# arm-pro-mini.net
KiCad netlist of a schematic drawn in EAGLE
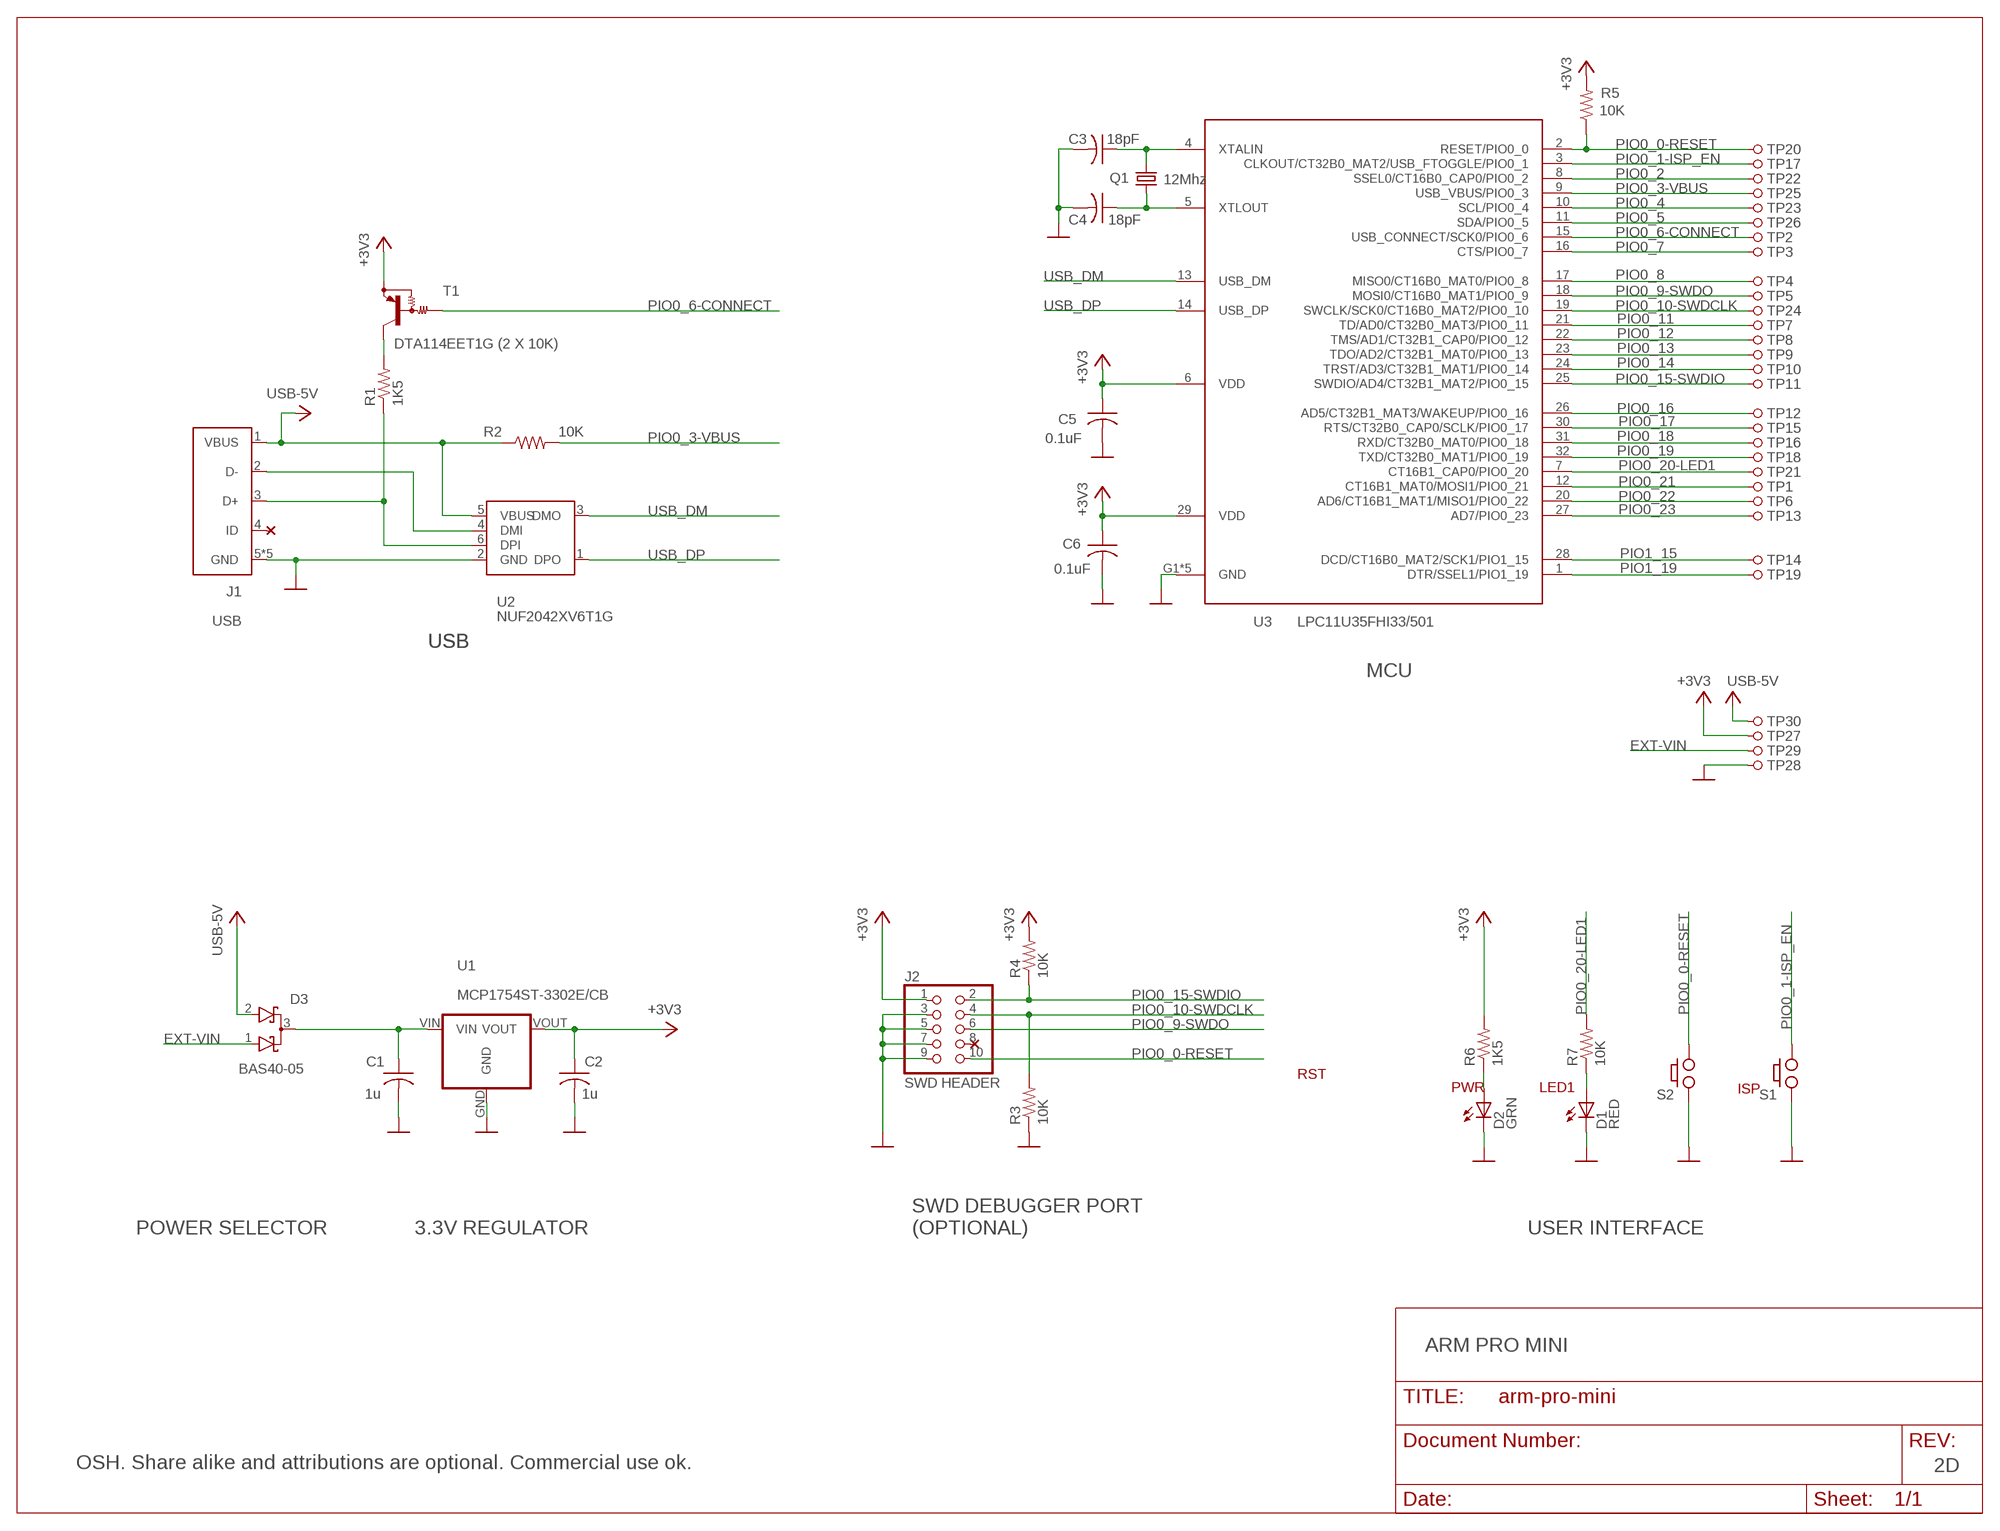
[diagram p0: schematic, sheet 1]

(export (version "E")
  (design (tool "Eeschema 10.0.6"))
  (components
    (comp (ref "C1")
      (value "1u")
      (footprint "eagle-import:C0603K")
      (libsource (lib "eagle-import") (part "CAPACITORC0603K"))
    )
    (comp (ref "C2")
      (value "1u")
      (footprint "eagle-import:C0603K")
      (libsource (lib "eagle-import") (part "CAPACITORC0603K"))
    )
    (comp (ref "C3")
      (value "18pF")
      (footprint "eagle-import:C0402K")
      (libsource (lib "eagle-import") (part "C-USC0402K"))
    )
    (comp (ref "C4")
      (value "18pF")
      (footprint "eagle-import:C0402K")
      (libsource (lib "eagle-import") (part "C-USC0402K"))
    )
    (comp (ref "C5")
      (value "0.1uF")
      (footprint "eagle-import:C0603K")
      (libsource (lib "eagle-import") (part "CAPACITORC0603K"))
    )
    (comp (ref "C6")
      (value "0.1uF")
      (footprint "eagle-import:C0603K")
      (libsource (lib "eagle-import") (part "CAPACITORC0603K"))
    )
    (comp (ref "D1")
      (value "RED")
      (footprint "eagle-import:LED0603")
      (libsource (lib "eagle-import") (part "LED"))
    )
    (comp (ref "D2")
      (value "GRN")
      (footprint "eagle-import:LED0603")
      (libsource (lib "eagle-import") (part "LED"))
    )
    (comp (ref "D3")
      (value "BAS40-05")
      (footprint "eagle-import:SOT23")
      (libsource (lib "eagle-import") (part "BAS40-05"))
    )
    (comp (ref "J1")
      (value "USB")
      (footprint "eagle-import:USB-MICRO")
      (libsource (lib "eagle-import") (part "USB"))
    )
    (comp (ref "J2")
      (value "SWD HEADER")
      (footprint "eagle-import:SWD-HEADER")
      (libsource (lib "eagle-import") (part "SWD-HEADER"))
    )
    (comp (ref "Q1")
      (value "12Mhz")
      (footprint "eagle-import:CRYSTAL")
      (libsource (lib "eagle-import") (part "CRYSTALCTS406"))
    )
    (comp (ref "R1")
      (value "1K5")
      (footprint "eagle-import:R0402")
      (libsource (lib "eagle-import") (part "R-US_R0402"))
    )
    (comp (ref "R2")
      (value "10K")
      (footprint "eagle-import:R0402")
      (libsource (lib "eagle-import") (part "R-US_R0402"))
    )
    (comp (ref "R3")
      (value "10K")
      (footprint "eagle-import:R0402")
      (libsource (lib "eagle-import") (part "R-US_R0402"))
    )
    (comp (ref "R4")
      (value "10K")
      (footprint "eagle-import:R0402")
      (libsource (lib "eagle-import") (part "R-US_R0402"))
    )
    (comp (ref "R5")
      (value "10K")
      (footprint "eagle-import:R0402")
      (libsource (lib "eagle-import") (part "R-US_R0402"))
    )
    (comp (ref "R6")
      (value "1K5")
      (footprint "eagle-import:R0402")
      (libsource (lib "eagle-import") (part "R-US_R0402"))
    )
    (comp (ref "R7")
      (value "10K")
      (footprint "eagle-import:R0402")
      (libsource (lib "eagle-import") (part "R-US_R0402"))
    )
    (comp (ref "S1")
      (value "PUSH_BUTTON")
      (footprint "eagle-import:PUSH_BUTTON")
      (libsource (lib "eagle-import") (part "PUSH_BUTTON"))
    )
    (comp (ref "S2")
      (value "PUSH_BUTTON")
      (footprint "eagle-import:PUSH_BUTTON")
      (libsource (lib "eagle-import") (part "PUSH_BUTTON"))
    )
    (comp (ref "T1")
      (value "DTA114EET1G (2 X 10K)")
      (footprint "eagle-import:SC75-BEC")
      (libsource (lib "eagle-import") (part "PNP_RESISTORS"))
    )
    (comp (ref "TP1")
      (value "HDR1")
      (footprint "eagle-import:1X01")
      (libsource (lib "eagle-import") (part "PINHD-1X1"))
    )
    (comp (ref "TP2")
      (value "HDR1")
      (footprint "eagle-import:1X01")
      (libsource (lib "eagle-import") (part "PINHD-1X1"))
    )
    (comp (ref "TP3")
      (value "HDR1")
      (footprint "eagle-import:1X01")
      (libsource (lib "eagle-import") (part "PINHD-1X1"))
    )
    (comp (ref "TP4")
      (value "HDR1")
      (footprint "eagle-import:1X01")
      (libsource (lib "eagle-import") (part "PINHD-1X1"))
    )
    (comp (ref "TP5")
      (value "HDR1")
      (footprint "eagle-import:1X01")
      (libsource (lib "eagle-import") (part "PINHD-1X1"))
    )
    (comp (ref "TP6")
      (value "HDR1")
      (footprint "eagle-import:1X01")
      (libsource (lib "eagle-import") (part "PINHD-1X1"))
    )
    (comp (ref "TP7")
      (value "HDR1")
      (footprint "eagle-import:1X01")
      (libsource (lib "eagle-import") (part "PINHD-1X1"))
    )
    (comp (ref "TP8")
      (value "HDR1")
      (footprint "eagle-import:1X01")
      (libsource (lib "eagle-import") (part "PINHD-1X1"))
    )
    (comp (ref "TP9")
      (value "HDR1")
      (footprint "eagle-import:1X01")
      (libsource (lib "eagle-import") (part "PINHD-1X1"))
    )
    (comp (ref "TP10")
      (value "HDR1")
      (footprint "eagle-import:1X01")
      (libsource (lib "eagle-import") (part "PINHD-1X1"))
    )
    (comp (ref "TP11")
      (value "HDR1")
      (footprint "eagle-import:1X01")
      (libsource (lib "eagle-import") (part "PINHD-1X1"))
    )
    (comp (ref "TP12")
      (value "HDR1")
      (footprint "eagle-import:1X01")
      (libsource (lib "eagle-import") (part "PINHD-1X1"))
    )
    (comp (ref "TP13")
      (value "HDR1")
      (footprint "eagle-import:1X01")
      (libsource (lib "eagle-import") (part "PINHD-1X1"))
    )
    (comp (ref "TP14")
      (value "HDR1")
      (footprint "eagle-import:1X01")
      (libsource (lib "eagle-import") (part "PINHD-1X1"))
    )
    (comp (ref "TP15")
      (value "HDR1")
      (footprint "eagle-import:1X01")
      (libsource (lib "eagle-import") (part "PINHD-1X1"))
    )
    (comp (ref "TP16")
      (value "HDR1")
      (footprint "eagle-import:1X01")
      (libsource (lib "eagle-import") (part "PINHD-1X1"))
    )
    (comp (ref "TP17")
      (value "HDR1")
      (footprint "eagle-import:1X01")
      (libsource (lib "eagle-import") (part "PINHD-1X1"))
    )
    (comp (ref "TP18")
      (value "HDR1")
      (footprint "eagle-import:1X01")
      (libsource (lib "eagle-import") (part "PINHD-1X1"))
    )
    (comp (ref "TP19")
      (value "HDR1")
      (footprint "eagle-import:1X01")
      (libsource (lib "eagle-import") (part "PINHD-1X1"))
    )
    (comp (ref "TP20")
      (value "HDR1")
      (footprint "eagle-import:1X01")
      (libsource (lib "eagle-import") (part "PINHD-1X1"))
    )
    (comp (ref "TP21")
      (value "HDR1")
      (footprint "eagle-import:1X01")
      (libsource (lib "eagle-import") (part "PINHD-1X1"))
    )
    (comp (ref "TP22")
      (value "HDR1")
      (footprint "eagle-import:1X01")
      (libsource (lib "eagle-import") (part "PINHD-1X1"))
    )
    (comp (ref "TP23")
      (value "HDR1")
      (footprint "eagle-import:1X01")
      (libsource (lib "eagle-import") (part "PINHD-1X1"))
    )
    (comp (ref "TP24")
      (value "HDR1")
      (footprint "eagle-import:1X01")
      (libsource (lib "eagle-import") (part "PINHD-1X1"))
    )
    (comp (ref "TP25")
      (value "HDR1")
      (footprint "eagle-import:1X01")
      (libsource (lib "eagle-import") (part "PINHD-1X1"))
    )
    (comp (ref "TP26")
      (value "HDR1")
      (footprint "eagle-import:1X01")
      (libsource (lib "eagle-import") (part "PINHD-1X1"))
    )
    (comp (ref "TP27")
      (value "HDR1")
      (footprint "eagle-import:1X01")
      (libsource (lib "eagle-import") (part "PINHD-1X1"))
    )
    (comp (ref "TP28")
      (value "HDR1")
      (footprint "eagle-import:1X01")
      (libsource (lib "eagle-import") (part "PINHD-1X1"))
    )
    (comp (ref "TP29")
      (value "HDR1")
      (footprint "eagle-import:1X01")
      (libsource (lib "eagle-import") (part "PINHD-1X1"))
    )
    (comp (ref "TP30")
      (value "HDR1")
      (footprint "eagle-import:1X01")
      (libsource (lib "eagle-import") (part "PINHD-1X1"))
    )
    (comp (ref "U1")
      (value "MCP1754ST-3302E/CB")
      (footprint "eagle-import:SOT-23A")
      (libsource (lib "eagle-import") (part "LDO"))
    )
    (comp (ref "U2")
      (value "NUF2042XV6T1G")
      (footprint "eagle-import:SOT-563")
      (libsource (lib "eagle-import") (part "USB_FILTER"))
    )
    (comp (ref "U3")
      (value "LPC11U35FHI33/501")
      (footprint "eagle-import:HVQFN33-5MM")
      (libsource (lib "eagle-import") (part "LPC11U35FHN33/501"))
    )
  )
  (nets
    (net (code "1") (name "+3V3") (class "Default")
      (node (ref "C2") (pin "1") (pinfunction "1_1") (pintype "passive"))
      (node (ref "C5") (pin "1") (pinfunction "1_1") (pintype "passive"))
      (node (ref "C6") (pin "1") (pinfunction "1_1") (pintype "passive"))
      (node (ref "J2") (pin "1") (pinfunction "1_1") (pintype "passive"))
      (node (ref "R4") (pin "2") (pinfunction "2_2") (pintype "passive"))
      (node (ref "R5") (pin "2") (pinfunction "2_2") (pintype "passive"))
      (node (ref "R6") (pin "2") (pinfunction "2_2") (pintype "passive"))
      (node (ref "T1") (pin "E") (pinfunction "E_E") (pintype "passive"))
      (node (ref "TP27") (pin "1") (pinfunction "1_1") (pintype "passive"))
      (node (ref "U1") (pin "VOUT") (pinfunction "VOUT_VOUT") (pintype "power_in"))
      (node (ref "U3") (pin "29") (pinfunction "VDD_29") (pintype "bidirectional"))
      (node (ref "U3") (pin "6") (pinfunction "VDD_6") (pintype "bidirectional"))
    )
    (net (code "2") (name "/EXT-VIN") (class "Default")
      (node (ref "D3") (pin "1") (pinfunction "A1_1") (pintype "passive"))
      (node (ref "TP29") (pin "1") (pinfunction "1_1") (pintype "passive"))
    )
    (net (code "3") (name "/PIO0_0-RESET") (class "Default")
      (node (ref "J2") (pin "10") (pinfunction "10_10") (pintype "passive"))
      (node (ref "R5") (pin "1") (pinfunction "1_1") (pintype "passive"))
      (node (ref "S2") (pin "B2") (pinfunction "2_B2") (pintype "passive"))
      (node (ref "TP20") (pin "1") (pinfunction "1_1") (pintype "passive"))
      (node (ref "U3") (pin "2") (pinfunction "RESET/PIO0_0_2") (pintype "bidirectional"))
    )
    (net (code "4") (name "/PIO0_1-ISP_EN") (class "Default")
      (node (ref "S1") (pin "B2") (pinfunction "2_B2") (pintype "passive"))
      (node (ref "TP17") (pin "1") (pinfunction "1_1") (pintype "passive"))
      (node (ref "U3") (pin "3") (pinfunction "CLKOUT/CT32B0_MAT2/USB_FTOGGLE/PIO0_1_3") (pintype "bidirectional"))
    )
    (net (code "5") (name "/PIO0_2") (class "Default")
      (node (ref "TP22") (pin "1") (pinfunction "1_1") (pintype "passive"))
      (node (ref "U3") (pin "8") (pinfunction "SSEL0/CT16B0_CAP0/PIO0_2_8") (pintype "bidirectional"))
    )
    (net (code "6") (name "/PIO0_3-VBUS") (class "Default")
      (node (ref "R2") (pin "2") (pinfunction "2_2") (pintype "passive"))
      (node (ref "TP25") (pin "1") (pinfunction "1_1") (pintype "passive"))
      (node (ref "U3") (pin "9") (pinfunction "USB_VBUS/PIO0_3_9") (pintype "bidirectional"))
    )
    (net (code "7") (name "/PIO0_4") (class "Default")
      (node (ref "TP23") (pin "1") (pinfunction "1_1") (pintype "passive"))
      (node (ref "U3") (pin "10") (pinfunction "SCL/PIO0_4_10") (pintype "bidirectional"))
    )
    (net (code "8") (name "/PIO0_5") (class "Default")
      (node (ref "TP26") (pin "1") (pinfunction "1_1") (pintype "passive"))
      (node (ref "U3") (pin "11") (pinfunction "SDA/PIO0_5_11") (pintype "bidirectional"))
    )
    (net (code "9") (name "/PIO0_6-CONNECT") (class "Default")
      (node (ref "T1") (pin "B") (pinfunction "B_B") (pintype "passive"))
      (node (ref "TP2") (pin "1") (pinfunction "1_1") (pintype "passive"))
      (node (ref "U3") (pin "15") (pinfunction "USB_CONNECT/SCK0/PIO0_6_15") (pintype "bidirectional"))
    )
    (net (code "10") (name "/PIO0_7") (class "Default")
      (node (ref "TP3") (pin "1") (pinfunction "1_1") (pintype "passive"))
      (node (ref "U3") (pin "16") (pinfunction "CTS/PIO0_7_16") (pintype "bidirectional"))
    )
    (net (code "11") (name "/PIO0_8") (class "Default")
      (node (ref "TP4") (pin "1") (pinfunction "1_1") (pintype "passive"))
      (node (ref "U3") (pin "17") (pinfunction "MISO0/CT16B0_MAT0/PIO0_8_17") (pintype "bidirectional"))
    )
    (net (code "12") (name "/PIO0_9-SWDO") (class "Default")
      (node (ref "J2") (pin "6") (pinfunction "6_6") (pintype "passive"))
      (node (ref "TP5") (pin "1") (pinfunction "1_1") (pintype "passive"))
      (node (ref "U3") (pin "18") (pinfunction "MOSI0/CT16B0_MAT1/PIO0_9_18") (pintype "bidirectional"))
    )
    (net (code "13") (name "/PIO0_10-SWDCLK") (class "Default")
      (node (ref "J2") (pin "4") (pinfunction "4_4") (pintype "passive"))
      (node (ref "R3") (pin "2") (pinfunction "2_2") (pintype "passive"))
      (node (ref "TP24") (pin "1") (pinfunction "1_1") (pintype "passive"))
      (node (ref "U3") (pin "19") (pinfunction "SWCLK/SCK0/CT16B0_MAT2/PIO0_10_19") (pintype "bidirectional"))
    )
    (net (code "14") (name "/PIO0_11") (class "Default")
      (node (ref "TP7") (pin "1") (pinfunction "1_1") (pintype "passive"))
      (node (ref "U3") (pin "21") (pinfunction "TD/AD0/CT32B0_MAT3/PIO0_11_21") (pintype "bidirectional"))
    )
    (net (code "15") (name "/PIO0_12") (class "Default")
      (node (ref "TP8") (pin "1") (pinfunction "1_1") (pintype "passive"))
      (node (ref "U3") (pin "22") (pinfunction "TMS/AD1/CT32B1_CAP0/PIO0_12_22") (pintype "bidirectional"))
    )
    (net (code "16") (name "/PIO0_13") (class "Default")
      (node (ref "TP9") (pin "1") (pinfunction "1_1") (pintype "passive"))
      (node (ref "U3") (pin "23") (pinfunction "TDO/AD2/CT32B1_MAT0/PIO0_13_23") (pintype "bidirectional"))
    )
    (net (code "17") (name "/PIO0_14") (class "Default")
      (node (ref "TP10") (pin "1") (pinfunction "1_1") (pintype "passive"))
      (node (ref "U3") (pin "24") (pinfunction "TRST/AD3/CT32B1_MAT1/PIO0_14_24") (pintype "bidirectional"))
    )
    (net (code "18") (name "/PIO0_15-SWDIO") (class "Default")
      (node (ref "J2") (pin "2") (pinfunction "2_2") (pintype "passive"))
      (node (ref "R4") (pin "1") (pinfunction "1_1") (pintype "passive"))
      (node (ref "TP11") (pin "1") (pinfunction "1_1") (pintype "passive"))
      (node (ref "U3") (pin "25") (pinfunction "SWDIO/AD4/CT32B1_MAT2/PIO0_15_25") (pintype "bidirectional"))
    )
    (net (code "19") (name "/PIO0_16") (class "Default")
      (node (ref "TP12") (pin "1") (pinfunction "1_1") (pintype "passive"))
      (node (ref "U3") (pin "26") (pinfunction "AD5/CT32B1_MAT3/WAKEUP/PIO0_16_26") (pintype "bidirectional"))
    )
    (net (code "20") (name "/PIO0_17") (class "Default")
      (node (ref "TP15") (pin "1") (pinfunction "1_1") (pintype "passive"))
      (node (ref "U3") (pin "30") (pinfunction "RTS/CT32B0_CAP0/SCLK/PIO0_17_30") (pintype "bidirectional"))
    )
    (net (code "21") (name "/PIO0_18") (class "Default")
      (node (ref "TP16") (pin "1") (pinfunction "1_1") (pintype "passive"))
      (node (ref "U3") (pin "31") (pinfunction "RXD/CT32B0_MAT0/PIO0_18_31") (pintype "bidirectional"))
    )
    (net (code "22") (name "/PIO0_19") (class "Default")
      (node (ref "TP18") (pin "1") (pinfunction "1_1") (pintype "passive"))
      (node (ref "U3") (pin "32") (pinfunction "TXD/CT32B0_MAT1/PIO0_19_32") (pintype "bidirectional"))
    )
    (net (code "23") (name "/PIO0_20-LED1") (class "Default")
      (node (ref "R7") (pin "2") (pinfunction "2_2") (pintype "passive"))
      (node (ref "TP21") (pin "1") (pinfunction "1_1") (pintype "passive"))
      (node (ref "U3") (pin "7") (pinfunction "CT16B1_CAP0/PIO0_20_7") (pintype "bidirectional"))
    )
    (net (code "24") (name "/PIO0_21") (class "Default")
      (node (ref "TP1") (pin "1") (pinfunction "1_1") (pintype "passive"))
      (node (ref "U3") (pin "12") (pinfunction "CT16B1_MAT0/MOSI1/PIO0_21_12") (pintype "bidirectional"))
    )
    (net (code "25") (name "/PIO0_22") (class "Default")
      (node (ref "TP6") (pin "1") (pinfunction "1_1") (pintype "passive"))
      (node (ref "U3") (pin "20") (pinfunction "AD6/CT16B1_MAT1/MISO1/PIO0_22_20") (pintype "bidirectional"))
    )
    (net (code "26") (name "/PIO0_23") (class "Default")
      (node (ref "TP13") (pin "1") (pinfunction "1_1") (pintype "passive"))
      (node (ref "U3") (pin "27") (pinfunction "AD7/PIO0_23_27") (pintype "bidirectional"))
    )
    (net (code "27") (name "/PIO1_15") (class "Default")
      (node (ref "TP14") (pin "1") (pinfunction "1_1") (pintype "passive"))
      (node (ref "U3") (pin "28") (pinfunction "DCD/CT16B0_MAT2/SCK1/PIO1_15_28") (pintype "bidirectional"))
    )
    (net (code "28") (name "/PIO1_19") (class "Default")
      (node (ref "TP19") (pin "1") (pinfunction "1_1") (pintype "passive"))
      (node (ref "U3") (pin "1") (pinfunction "DTR/SSEL1/PIO1_19_1") (pintype "bidirectional"))
    )
    (net (code "29") (name "/USB_DM") (class "Default")
      (node (ref "U2") (pin "3") (pinfunction "DMO_3") (pintype "passive"))
      (node (ref "U3") (pin "13") (pinfunction "USB_DM_13") (pintype "bidirectional"))
    )
    (net (code "30") (name "/USB_DP") (class "Default")
      (node (ref "U2") (pin "1") (pinfunction "DPO_1") (pintype "passive"))
      (node (ref "U3") (pin "14") (pinfunction "USB_DP_14") (pintype "bidirectional"))
    )
    (net (code "31") (name "GND") (class "Default")
      (node (ref "C1") (pin "2") (pinfunction "2_2") (pintype "passive"))
      (node (ref "C2") (pin "2") (pinfunction "2_2") (pintype "passive"))
      (node (ref "C3") (pin "2") (pinfunction "2_2") (pintype "passive"))
      (node (ref "C4") (pin "2") (pinfunction "2_2") (pintype "passive"))
      (node (ref "C5") (pin "2") (pinfunction "2_2") (pintype "passive"))
      (node (ref "C6") (pin "2") (pinfunction "2_2") (pintype "passive"))
      (node (ref "D1") (pin "C") (pinfunction "C_C") (pintype "passive"))
      (node (ref "D2") (pin "C") (pinfunction "C_C") (pintype "passive"))
      (node (ref "J1") (pin "5") (pinfunction "GND_5") (pintype "bidirectional"))
      (node (ref "J1") (pin "G1") (pinfunction "GND_G1") (pintype "bidirectional"))
      (node (ref "J1") (pin "G2") (pinfunction "GND_G2") (pintype "bidirectional"))
      (node (ref "J1") (pin "G3") (pinfunction "GND_G3") (pintype "bidirectional"))
      (node (ref "J1") (pin "G4") (pinfunction "GND_G4") (pintype "bidirectional"))
      (node (ref "J2") (pin "3") (pinfunction "3_3") (pintype "passive"))
      (node (ref "J2") (pin "5") (pinfunction "5_5") (pintype "passive"))
      (node (ref "J2") (pin "7") (pinfunction "7_7") (pintype "passive"))
      (node (ref "J2") (pin "9") (pinfunction "9_9") (pintype "passive"))
      (node (ref "R3") (pin "1") (pinfunction "1_1") (pintype "passive"))
      (node (ref "S1") (pin "A1") (pinfunction "1_A1") (pintype "passive"))
      (node (ref "S2") (pin "A1") (pinfunction "1_A1") (pintype "passive"))
      (node (ref "TP28") (pin "1") (pinfunction "1_1") (pintype "passive"))
      (node (ref "U1") (pin "GND") (pinfunction "GND_GND") (pintype "power_in"))
      (node (ref "U2") (pin "2") (pinfunction "GND_2") (pintype "power_in"))
      (node (ref "U3") (pin "G1") (pinfunction "GND_G1") (pintype "bidirectional"))
      (node (ref "U3") (pin "G2") (pinfunction "GND_G2") (pintype "bidirectional"))
      (node (ref "U3") (pin "G3") (pinfunction "GND_G3") (pintype "bidirectional"))
      (node (ref "U3") (pin "G4") (pinfunction "GND_G4") (pintype "bidirectional"))
      (node (ref "U3") (pin "TAB") (pinfunction "GND_TAB") (pintype "bidirectional"))
    )
    (net (code "32") (name "Net-(D1-PadA)") (class "Default")
      (node (ref "D1") (pin "A") (pinfunction "A_A") (pintype "passive"))
      (node (ref "R7") (pin "1") (pinfunction "1_1") (pintype "passive"))
    )
    (net (code "33") (name "Net-(D2-PadA)") (class "Default")
      (node (ref "D2") (pin "A") (pinfunction "A_A") (pintype "passive"))
      (node (ref "R6") (pin "1") (pinfunction "1_1") (pintype "passive"))
    )
    (net (code "34") (name "Net-(D3-C)") (class "Default")
      (node (ref "C1") (pin "1") (pinfunction "1_1") (pintype "passive"))
      (node (ref "D3") (pin "3") (pinfunction "C_3") (pintype "passive"))
      (node (ref "U1") (pin "VIN") (pinfunction "VIN_VIN") (pintype "power_in"))
    )
    (net (code "35") (name "Net-(J1-D+)") (class "Default")
      (node (ref "J1") (pin "3") (pinfunction "D+_3") (pintype "bidirectional"))
      (node (ref "R1") (pin "1") (pinfunction "1_1") (pintype "passive"))
      (node (ref "U2") (pin "6") (pinfunction "DPI_6") (pintype "passive"))
    )
    (net (code "36") (name "Net-(J1-D-)") (class "Default")
      (node (ref "J1") (pin "2") (pinfunction "D-_2") (pintype "bidirectional"))
      (node (ref "U2") (pin "4") (pinfunction "DMI_4") (pintype "passive"))
    )
    (net (code "37") (name "Net-(Q1-2)") (class "Default")
      (node (ref "C3") (pin "1") (pinfunction "1_1") (pintype "passive"))
      (node (ref "Q1") (pin "3") (pinfunction "2_3") (pintype "passive"))
      (node (ref "U3") (pin "4") (pinfunction "XTALIN_4") (pintype "bidirectional"))
    )
    (net (code "38") (name "Net-(R1-Pad2)") (class "Default")
      (node (ref "R1") (pin "2") (pinfunction "2_2") (pintype "passive"))
      (node (ref "T1") (pin "C") (pinfunction "C_C") (pintype "passive"))
    )
    (net (code "39") (name "Net-(U3-XTLOUT)") (class "Default")
      (node (ref "C4") (pin "1") (pinfunction "1_1") (pintype "passive"))
      (node (ref "Q1") (pin "1") (pinfunction "1_1") (pintype "passive"))
      (node (ref "U3") (pin "5") (pinfunction "XTLOUT_5") (pintype "bidirectional"))
    )
    (net (code "40") (name "USB-5V") (class "Default")
      (node (ref "D3") (pin "2") (pinfunction "A2_2") (pintype "passive"))
      (node (ref "J1") (pin "1") (pinfunction "VBUS_1") (pintype "bidirectional"))
      (node (ref "R2") (pin "1") (pinfunction "1_1") (pintype "passive"))
      (node (ref "TP30") (pin "1") (pinfunction "1_1") (pintype "passive"))
      (node (ref "U2") (pin "5") (pinfunction "VBUS_5") (pintype "power_in"))
    )
    (net (code "41") (name "unconnected-(J1-ID-Pad4)") (class "Default")
      (node (ref "J1") (pin "4") (pinfunction "ID_4") (pintype "bidirectional"))
    )
    (net (code "42") (name "unconnected-(J2-Pad8)") (class "Default")
      (node (ref "J2") (pin "8") (pinfunction "8_8") (pintype "passive"))
    )
  )
)
